# Motor_Driver.net
KiCad netlist of a schematic drawn in EAGLE
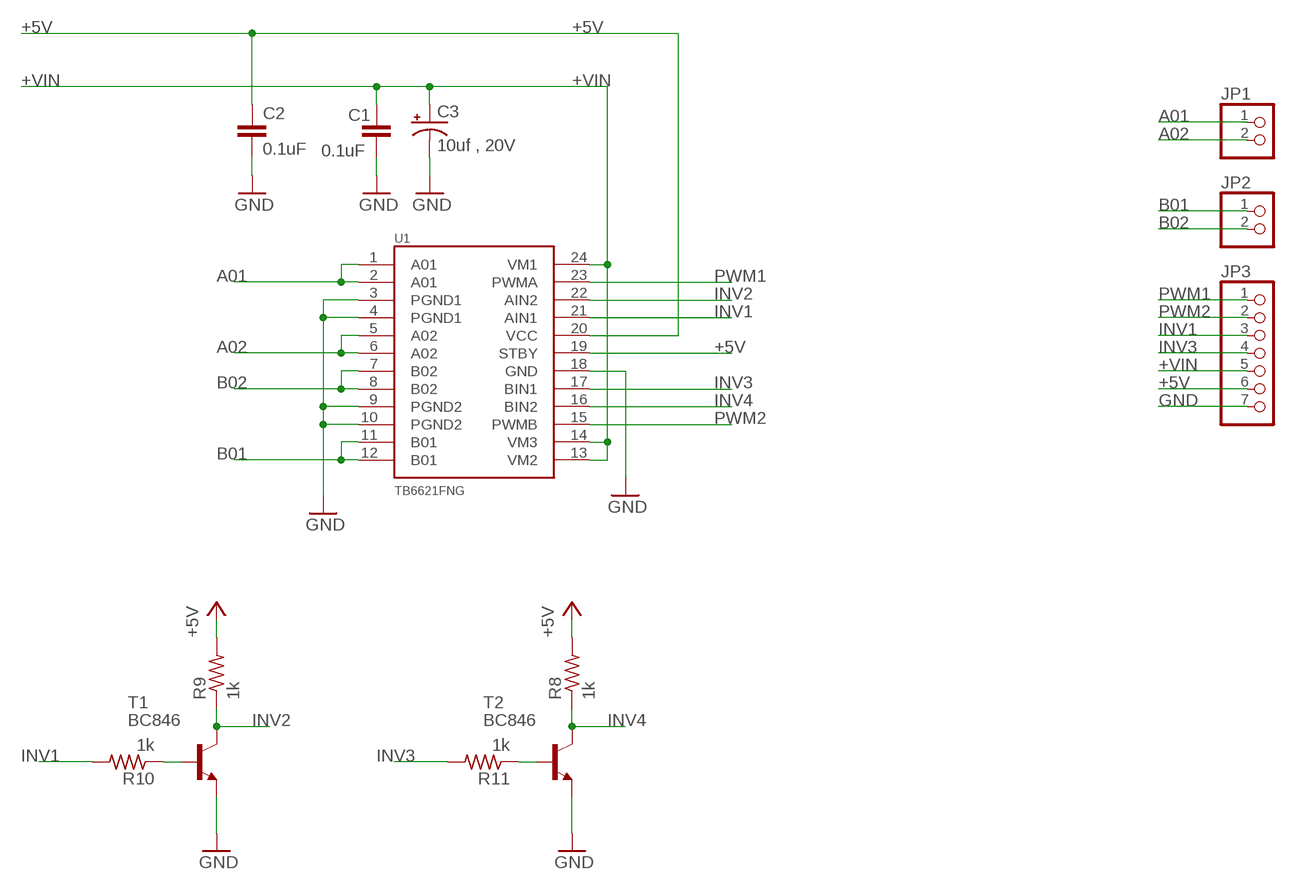
[diagram p0: schematic, sheet 1]

(export (version "E")
  (design (tool "Eeschema 10.0.6"))
  (components
    (comp (ref "C1")
      (value "0.1uF")
      (footprint "eagle-import:0402-CAP")
      (libsource (lib "eagle-import") (part "CAP0402-CAP"))
    )
    (comp (ref "C2")
      (value "0.1uF")
      (footprint "eagle-import:0402-CAP")
      (libsource (lib "eagle-import") (part "CAP0402-CAP"))
    )
    (comp (ref "C3")
      (value "10uf , 20V")
      (footprint "eagle-import:EIA3528")
      (libsource (lib "eagle-import") (part "CAP_POL3528"))
    )
    (comp (ref "JP1")
      (value "PINHD-1X2")
      (footprint "eagle-import:1X02")
      (libsource (lib "eagle-import") (part "PINHD-1X2"))
    )
    (comp (ref "JP2")
      (value "PINHD-1X2")
      (footprint "eagle-import:1X02")
      (libsource (lib "eagle-import") (part "PINHD-1X2"))
    )
    (comp (ref "JP3")
      (value "PINHD-1X7")
      (footprint "eagle-import:1X07")
      (libsource (lib "eagle-import") (part "PINHD-1X7"))
    )
    (comp (ref "R8")
      (value "1k")
      (footprint "eagle-import:R0603")
      (libsource (lib "eagle-import") (part "R-US_R0603"))
    )
    (comp (ref "R9")
      (value "1k")
      (footprint "eagle-import:R0603")
      (libsource (lib "eagle-import") (part "R-US_R0603"))
    )
    (comp (ref "R10")
      (value "1k")
      (footprint "eagle-import:R0603")
      (libsource (lib "eagle-import") (part "R-US_R0603"))
    )
    (comp (ref "R11")
      (value "1k")
      (footprint "eagle-import:R0603")
      (libsource (lib "eagle-import") (part "R-US_R0603"))
    )
    (comp (ref "T1")
      (value "BC846")
      (footprint "eagle-import:SOT23")
      (libsource (lib "eagle-import") (part "BC846"))
    )
    (comp (ref "T2")
      (value "BC846")
      (footprint "eagle-import:SOT23")
      (libsource (lib "eagle-import") (part "BC846"))
    )
    (comp (ref "U1")
      (value "TB6621FNG")
      (footprint "eagle-import:SSOP24")
      (libsource (lib "eagle-import") (part "TB6621FNG"))
    )
  )
  (nets
    (net (code "1") (name "+5V") (class "Default")
      (node (ref "C2") (pin "1") (pinfunction "1_1") (pintype "passive"))
      (node (ref "JP3") (pin "6") (pinfunction "6_6") (pintype "passive"))
      (node (ref "R8") (pin "2") (pinfunction "2_2") (pintype "passive"))
      (node (ref "R9") (pin "2") (pinfunction "2_2") (pintype "passive"))
      (node (ref "U1") (pin "19") (pinfunction "STBY_19") (pintype "bidirectional"))
      (node (ref "U1") (pin "20") (pinfunction "VCC_20") (pintype "bidirectional"))
    )
    (net (code "2") (name "/+VIN") (class "Default")
      (node (ref "C1") (pin "1") (pinfunction "1_1") (pintype "passive"))
      (node (ref "C3") (pin "A") (pinfunction "+_A") (pintype "passive"))
      (node (ref "JP3") (pin "5") (pinfunction "5_5") (pintype "passive"))
      (node (ref "U1") (pin "13") (pinfunction "VM2_13") (pintype "bidirectional"))
      (node (ref "U1") (pin "14") (pinfunction "VM3_14") (pintype "bidirectional"))
      (node (ref "U1") (pin "24") (pinfunction "VM1_24") (pintype "bidirectional"))
    )
    (net (code "3") (name "/A01") (class "Default")
      (node (ref "JP1") (pin "1") (pinfunction "1_1") (pintype "passive"))
      (node (ref "U1") (pin "1") (pinfunction "A01_1") (pintype "bidirectional"))
      (node (ref "U1") (pin "2") (pinfunction "A01_2") (pintype "bidirectional"))
    )
    (net (code "4") (name "/A02") (class "Default")
      (node (ref "JP1") (pin "2") (pinfunction "2_2") (pintype "passive"))
      (node (ref "U1") (pin "5") (pinfunction "A02_5") (pintype "bidirectional"))
      (node (ref "U1") (pin "6") (pinfunction "A02_6") (pintype "bidirectional"))
    )
    (net (code "5") (name "/B01") (class "Default")
      (node (ref "JP2") (pin "1") (pinfunction "1_1") (pintype "passive"))
      (node (ref "U1") (pin "11") (pinfunction "B01_11") (pintype "bidirectional"))
      (node (ref "U1") (pin "12") (pinfunction "B01_12") (pintype "bidirectional"))
    )
    (net (code "6") (name "/B02") (class "Default")
      (node (ref "JP2") (pin "2") (pinfunction "2_2") (pintype "passive"))
      (node (ref "U1") (pin "7") (pinfunction "B02_7") (pintype "bidirectional"))
      (node (ref "U1") (pin "8") (pinfunction "B02_8") (pintype "bidirectional"))
    )
    (net (code "7") (name "/INV1") (class "Default")
      (node (ref "JP3") (pin "3") (pinfunction "3_3") (pintype "passive"))
      (node (ref "R10") (pin "2") (pinfunction "2_2") (pintype "passive"))
      (node (ref "U1") (pin "21") (pinfunction "AIN1_21") (pintype "bidirectional"))
    )
    (net (code "8") (name "/INV2") (class "Default")
      (node (ref "R9") (pin "1") (pinfunction "1_1") (pintype "passive"))
      (node (ref "T1") (pin "3") (pinfunction "C_3") (pintype "passive"))
      (node (ref "U1") (pin "22") (pinfunction "AIN2_22") (pintype "bidirectional"))
    )
    (net (code "9") (name "/INV3") (class "Default")
      (node (ref "JP3") (pin "4") (pinfunction "4_4") (pintype "passive"))
      (node (ref "R11") (pin "2") (pinfunction "2_2") (pintype "passive"))
      (node (ref "U1") (pin "17") (pinfunction "BIN1_17") (pintype "bidirectional"))
    )
    (net (code "10") (name "/INV4") (class "Default")
      (node (ref "R8") (pin "1") (pinfunction "1_1") (pintype "passive"))
      (node (ref "T2") (pin "3") (pinfunction "C_3") (pintype "passive"))
      (node (ref "U1") (pin "16") (pinfunction "BIN2_16") (pintype "bidirectional"))
    )
    (net (code "11") (name "/PWM1") (class "Default")
      (node (ref "JP3") (pin "1") (pinfunction "1_1") (pintype "passive"))
      (node (ref "U1") (pin "23") (pinfunction "PWMA_23") (pintype "bidirectional"))
    )
    (net (code "12") (name "/PWM2") (class "Default")
      (node (ref "JP3") (pin "2") (pinfunction "2_2") (pintype "passive"))
      (node (ref "U1") (pin "15") (pinfunction "PWMB_15") (pintype "bidirectional"))
    )
    (net (code "13") (name "GND") (class "Default")
      (node (ref "C1") (pin "2") (pinfunction "2_2") (pintype "passive"))
      (node (ref "C2") (pin "2") (pinfunction "2_2") (pintype "passive"))
      (node (ref "C3") (pin "C") (pinfunction "-_C") (pintype "passive"))
      (node (ref "JP3") (pin "7") (pinfunction "7_7") (pintype "passive"))
      (node (ref "T1") (pin "2") (pinfunction "E_2") (pintype "passive"))
      (node (ref "T2") (pin "2") (pinfunction "E_2") (pintype "passive"))
      (node (ref "U1") (pin "10") (pinfunction "PGND2_10") (pintype "bidirectional"))
      (node (ref "U1") (pin "18") (pinfunction "GND_18") (pintype "bidirectional"))
      (node (ref "U1") (pin "3") (pinfunction "PGND1_3") (pintype "bidirectional"))
      (node (ref "U1") (pin "4") (pinfunction "PGND1_4") (pintype "bidirectional"))
      (node (ref "U1") (pin "9") (pinfunction "PGND2_9") (pintype "bidirectional"))
    )
    (net (code "14") (name "Net-(T1-B)") (class "Default")
      (node (ref "R10") (pin "1") (pinfunction "1_1") (pintype "passive"))
      (node (ref "T1") (pin "1") (pinfunction "B_1") (pintype "passive"))
    )
    (net (code "15") (name "Net-(T2-B)") (class "Default")
      (node (ref "R11") (pin "1") (pinfunction "1_1") (pintype "passive"))
      (node (ref "T2") (pin "1") (pinfunction "B_1") (pintype "passive"))
    )
  )
)
